# HASP_PARASITE.net
KiCad netlist of a schematic drawn in EAGLE
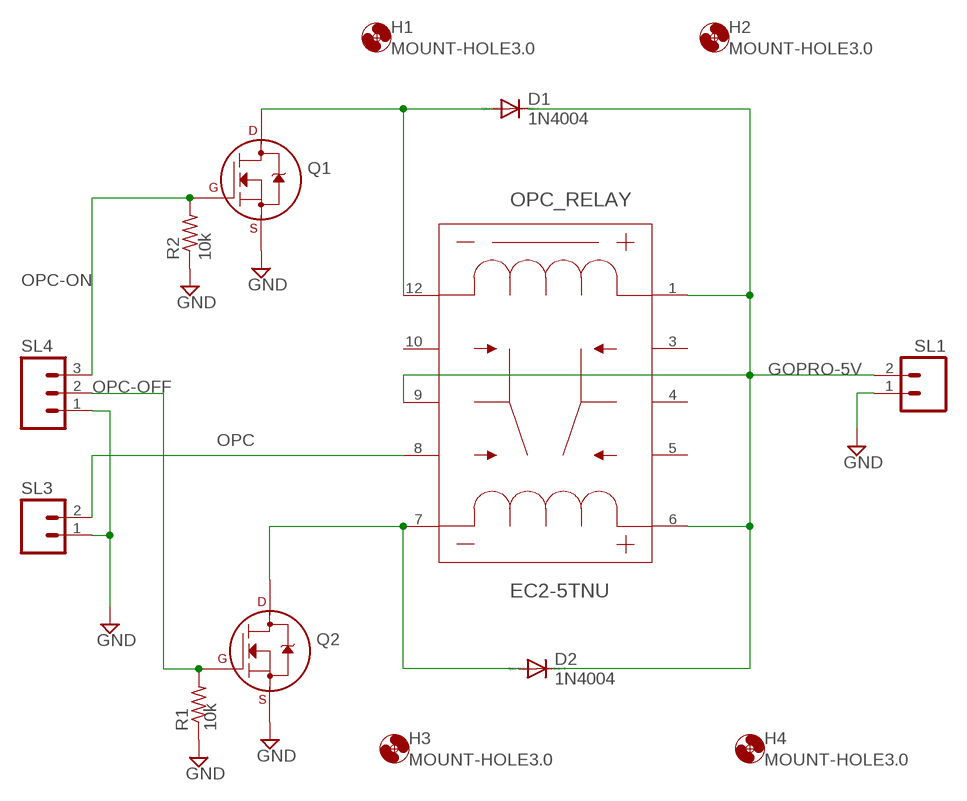
[diagram p0: schematic, sheet 1]

(export (version "E")
  (design (tool "Eeschema 10.0.6"))
  (components
    (comp (ref "D1")
      (value "1N4004")
      (footprint "eagle-import:DO41-10")
      (libsource (lib "eagle-import") (part "1N4004"))
    )
    (comp (ref "D2")
      (value "1N4004")
      (footprint "eagle-import:DO41-10")
      (libsource (lib "eagle-import") (part "1N4004"))
    )
    (comp (ref "H1")
      (value "MOUNT-HOLE3.0")
      (footprint "eagle-import:3,0")
      (libsource (lib "eagle-import") (part "MOUNT-HOLE3.0"))
    )
    (comp (ref "H2")
      (value "MOUNT-HOLE3.0")
      (footprint "eagle-import:3,0")
      (libsource (lib "eagle-import") (part "MOUNT-HOLE3.0"))
    )
    (comp (ref "H3")
      (value "MOUNT-HOLE3.0")
      (footprint "eagle-import:3,0")
      (libsource (lib "eagle-import") (part "MOUNT-HOLE3.0"))
    )
    (comp (ref "H4")
      (value "MOUNT-HOLE3.0")
      (footprint "eagle-import:3,0")
      (libsource (lib "eagle-import") (part "MOUNT-HOLE3.0"))
    )
    (comp (ref "OPC_RELAY")
      (value "EC2-5TNU")
      (footprint "eagle-import:EC2TNU")
      (fields (field (name "MANUFACTURER_PART_NUMBER") "EC25TNU"))
      (libsource (lib "eagle-import") (part "EC2-5TNU"))
    )
    (comp (ref "Q1")
      (value "2N7000_TO92")
      (footprint "eagle-import:TO-92")
      (libsource (lib "eagle-import") (part "2N700_TO920"))
    )
    (comp (ref "Q2")
      (value "2N7000_TO92")
      (footprint "eagle-import:TO-92")
      (libsource (lib "eagle-import") (part "2N700_TO920"))
    )
    (comp (ref "R1")
      (value "R-US_0207/7")
      (footprint "eagle-import:0207_7")
      (libsource (lib "eagle-import") (part "R-US_0207/7"))
    )
    (comp (ref "R2")
      (value "R-US_0207/7")
      (footprint "eagle-import:0207_7")
      (libsource (lib "eagle-import") (part "R-US_0207/7"))
    )
    (comp (ref "SL1")
      (value "M02")
      (footprint "eagle-import:02P")
      (libsource (lib "eagle-import") (part "M02"))
    )
    (comp (ref "SL3")
      (value "M02")
      (footprint "eagle-import:02P")
      (libsource (lib "eagle-import") (part "M02"))
    )
    (comp (ref "SL4")
      (value "M03")
      (footprint "eagle-import:03P")
      (libsource (lib "eagle-import") (part "M03"))
    )
  )
  (nets
    (net (code "1") (name "/GOPRO-5V") (class "Default")
      (node (ref "D1") (pin "C") (pinfunction "C_C") (pintype "passive"))
      (node (ref "D2") (pin "C") (pinfunction "C_C") (pintype "passive"))
      (node (ref "OPC_RELAY") (pin "1") (pinfunction "1_1") (pintype "passive"))
      (node (ref "OPC_RELAY") (pin "6") (pinfunction "5_6") (pintype "passive"))
      (node (ref "OPC_RELAY") (pin "9") (pinfunction "8_9") (pintype "passive"))
      (node (ref "SL1") (pin "2") (pinfunction "2_2") (pintype "passive"))
    )
    (net (code "2") (name "/OPC") (class "Default")
      (node (ref "OPC_RELAY") (pin "8") (pinfunction "7_8") (pintype "passive"))
      (node (ref "SL3") (pin "2") (pinfunction "2_2") (pintype "passive"))
    )
    (net (code "3") (name "/OPC-OFF") (class "Default")
      (node (ref "Q2") (pin "2") (pinfunction "G_2") (pintype "tri_state"))
      (node (ref "R1") (pin "2") (pinfunction "2_2") (pintype "passive"))
      (node (ref "SL4") (pin "2") (pinfunction "2_2") (pintype "passive"))
    )
    (net (code "4") (name "/OPC-ON") (class "Default")
      (node (ref "Q1") (pin "2") (pinfunction "G_2") (pintype "tri_state"))
      (node (ref "R2") (pin "2") (pinfunction "2_2") (pintype "passive"))
      (node (ref "SL4") (pin "3") (pinfunction "3_3") (pintype "passive"))
    )
    (net (code "5") (name "GND") (class "Default")
      (node (ref "Q1") (pin "1") (pinfunction "S_1") (pintype "bidirectional"))
      (node (ref "Q2") (pin "1") (pinfunction "S_1") (pintype "bidirectional"))
      (node (ref "R1") (pin "1") (pinfunction "1_1") (pintype "passive"))
      (node (ref "R2") (pin "1") (pinfunction "1_1") (pintype "passive"))
      (node (ref "SL1") (pin "1") (pinfunction "1_1") (pintype "passive"))
      (node (ref "SL3") (pin "1") (pinfunction "1_1") (pintype "passive"))
      (node (ref "SL4") (pin "1") (pinfunction "1_1") (pintype "passive"))
    )
    (net (code "6") (name "Net-(OPC_RELAY-6)") (class "Default")
      (node (ref "D2") (pin "A") (pinfunction "A_A") (pintype "passive"))
      (node (ref "OPC_RELAY") (pin "7") (pinfunction "6_7") (pintype "passive"))
      (node (ref "Q2") (pin "3") (pinfunction "D_3") (pintype "bidirectional"))
    )
    (net (code "7") (name "Net-(OPC_RELAY-10)") (class "Default")
      (node (ref "D1") (pin "A") (pinfunction "A_A") (pintype "passive"))
      (node (ref "OPC_RELAY") (pin "12") (pinfunction "10_12") (pintype "passive"))
      (node (ref "Q1") (pin "3") (pinfunction "D_3") (pintype "bidirectional"))
    )
    (net (code "8") (name "unconnected-(OPC_RELAY-2-Pad3)") (class "Default")
      (node (ref "OPC_RELAY") (pin "3") (pinfunction "2_3") (pintype "passive"))
    )
    (net (code "9") (name "unconnected-(OPC_RELAY-3-Pad4)") (class "Default")
      (node (ref "OPC_RELAY") (pin "4") (pinfunction "3_4") (pintype "passive"))
    )
    (net (code "10") (name "unconnected-(OPC_RELAY-4-Pad5)") (class "Default")
      (node (ref "OPC_RELAY") (pin "5") (pinfunction "4_5") (pintype "passive"))
    )
    (net (code "11") (name "unconnected-(OPC_RELAY-9-Pad10)") (class "Default")
      (node (ref "OPC_RELAY") (pin "10") (pinfunction "9_10") (pintype "passive"))
    )
  )
)
